# M-LVDS_PHY.net
KiCad netlist of a schematic drawn in Altium Designer
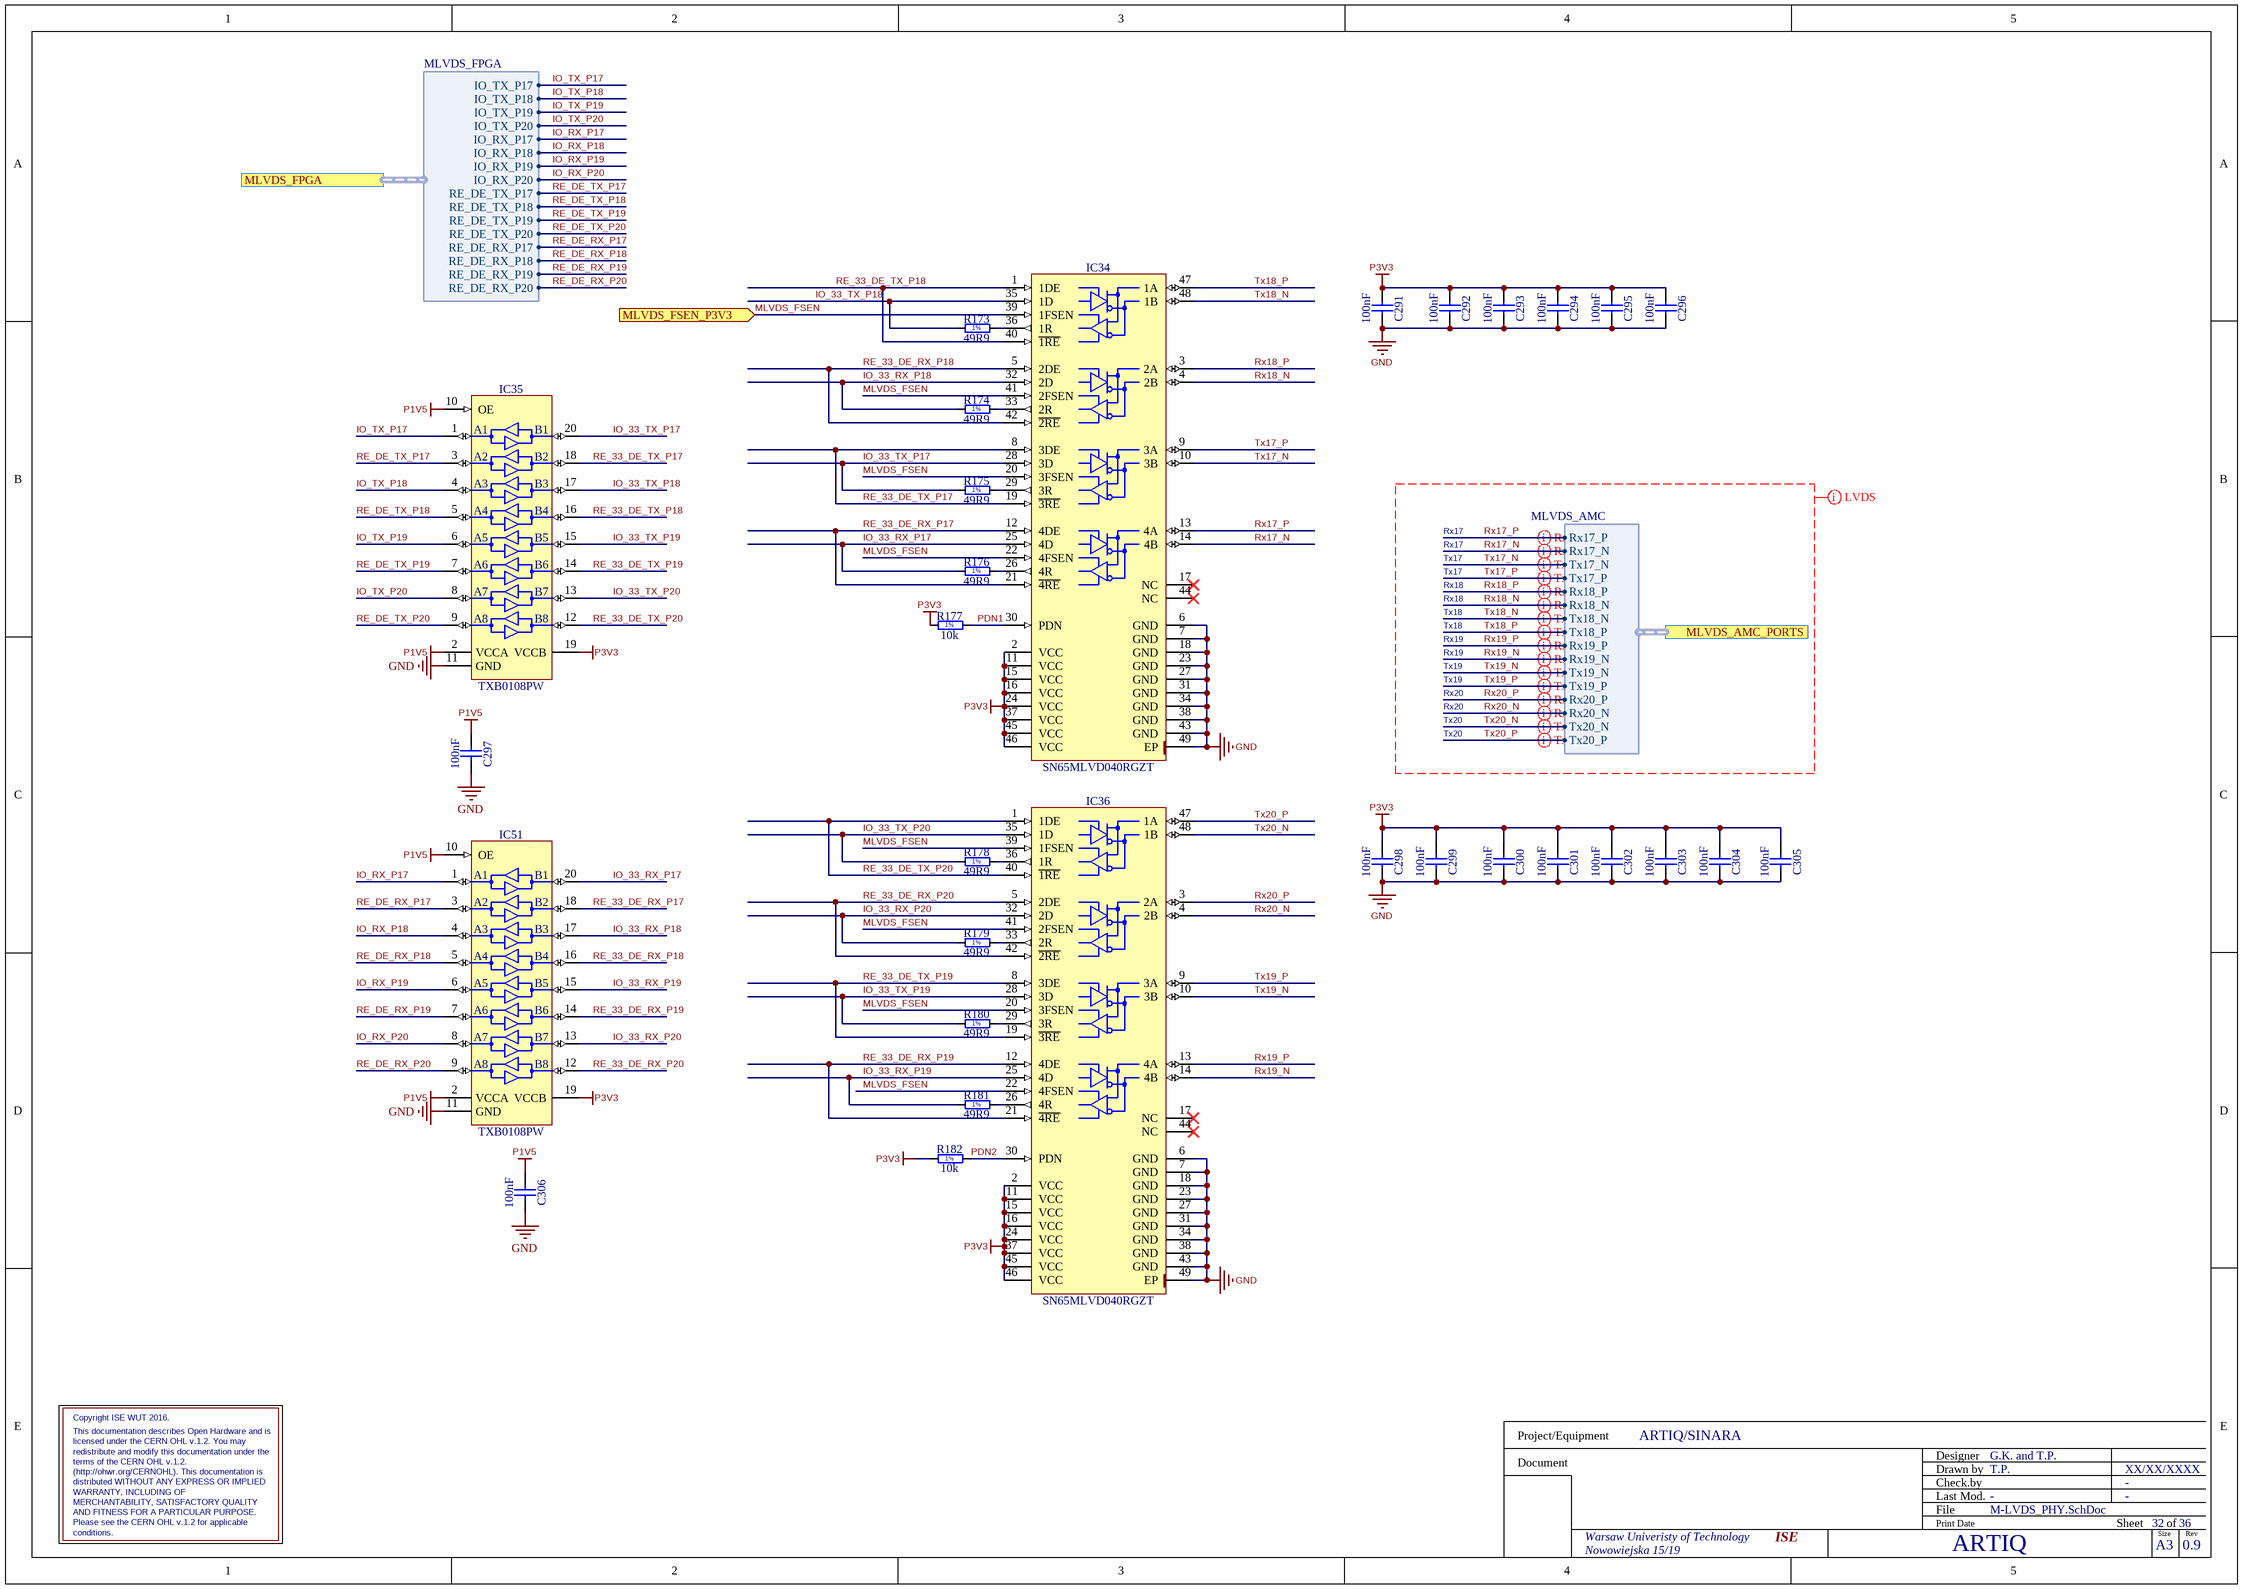
[diagram p0: M-LVDS_PHY.SchDoc]

(export (version "E")
  (design (tool "Eeschema 10.0.6"))
  (components
    (comp (ref "C291")
      (value "100nF")
      (footprint "CAPC0603X33N")
      (description "Non-polarised capacitor")
      (fields
        (field (name "MANUFACTURER PART NUMBER") "CC0201_100NF_6.3V_10%_X5R")
        (field (name "MANUFACTURER") "GENERIC")
        (field (name "AUTHOR") "CERN DEM JLC")
      )
      (libsource (lib "Capacitors") (part "Capacitor - non polarized"))
    )
    (comp (ref "C292")
      (value "100nF")
      (footprint "CAPC0603X33N")
      (description "Non-polarised capacitor")
      (fields
        (field (name "MANUFACTURER PART NUMBER") "CC0201_100NF_6.3V_10%_X5R")
        (field (name "MANUFACTURER") "GENERIC")
        (field (name "AUTHOR") "CERN DEM JLC")
      )
      (libsource (lib "Capacitors") (part "Capacitor - non polarized"))
    )
    (comp (ref "C293")
      (value "100nF")
      (footprint "CAPC0603X33N")
      (description "Non-polarised capacitor")
      (fields
        (field (name "MANUFACTURER PART NUMBER") "CC0201_100NF_6.3V_10%_X5R")
        (field (name "MANUFACTURER") "GENERIC")
        (field (name "AUTHOR") "CERN DEM JLC")
      )
      (libsource (lib "Capacitors") (part "Capacitor - non polarized"))
    )
    (comp (ref "C294")
      (value "100nF")
      (footprint "CAPC0603X33N")
      (description "Non-polarised capacitor")
      (fields
        (field (name "MANUFACTURER PART NUMBER") "CC0201_100NF_6.3V_10%_X5R")
        (field (name "MANUFACTURER") "GENERIC")
        (field (name "AUTHOR") "CERN DEM JLC")
      )
      (libsource (lib "Capacitors") (part "Capacitor - non polarized"))
    )
    (comp (ref "C295")
      (value "100nF")
      (footprint "CAPC0603X33N")
      (description "Non-polarised capacitor")
      (fields
        (field (name "MANUFACTURER PART NUMBER") "CC0201_100NF_6.3V_10%_X5R")
        (field (name "MANUFACTURER") "GENERIC")
        (field (name "AUTHOR") "CERN DEM JLC")
      )
      (libsource (lib "Capacitors") (part "Capacitor - non polarized"))
    )
    (comp (ref "C296")
      (value "100nF")
      (footprint "CAPC0603X33N")
      (description "Non-polarised capacitor")
      (fields
        (field (name "MANUFACTURER PART NUMBER") "CC0201_100NF_6.3V_10%_X5R")
        (field (name "MANUFACTURER") "GENERIC")
        (field (name "AUTHOR") "CERN DEM JLC")
      )
      (libsource (lib "Capacitors") (part "Capacitor - non polarized"))
    )
    (comp (ref "C297")
      (value "100nF")
      (footprint "CAPC0603X33N")
      (description "Non-polarised capacitor")
      (fields
        (field (name "MANUFACTURER PART NUMBER") "CC0201_100NF_6.3V_10%_X5R")
        (field (name "MANUFACTURER") "GENERIC")
        (field (name "AUTHOR") "CERN DEM JLC")
      )
      (libsource (lib "Capacitors") (part "Capacitor - non polarized"))
    )
    (comp (ref "C298")
      (value "100nF")
      (footprint "CAPC0603X33N")
      (description "Non-polarised capacitor")
      (fields
        (field (name "MANUFACTURER PART NUMBER") "CC0201_100NF_6.3V_10%_X5R")
        (field (name "MANUFACTURER") "GENERIC")
        (field (name "AUTHOR") "CERN DEM JLC")
      )
      (libsource (lib "Capacitors") (part "Capacitor - non polarized"))
    )
    (comp (ref "C299")
      (value "100nF")
      (footprint "CAPC0603X33N")
      (description "Non-polarised capacitor")
      (fields
        (field (name "MANUFACTURER PART NUMBER") "CC0201_100NF_6.3V_10%_X5R")
        (field (name "MANUFACTURER") "GENERIC")
        (field (name "AUTHOR") "CERN DEM JLC")
      )
      (libsource (lib "Capacitors") (part "Capacitor - non polarized"))
    )
    (comp (ref "C300")
      (value "100nF")
      (footprint "CAPC0603X33N")
      (description "Non-polarised capacitor")
      (fields
        (field (name "MANUFACTURER PART NUMBER") "CC0201_100NF_6.3V_10%_X5R")
        (field (name "MANUFACTURER") "GENERIC")
        (field (name "AUTHOR") "CERN DEM JLC")
      )
      (libsource (lib "Capacitors") (part "Capacitor - non polarized"))
    )
    (comp (ref "C301")
      (value "100nF")
      (footprint "CAPC0603X33N")
      (description "Non-polarised capacitor")
      (fields
        (field (name "MANUFACTURER PART NUMBER") "CC0201_100NF_6.3V_10%_X5R")
        (field (name "MANUFACTURER") "GENERIC")
        (field (name "AUTHOR") "CERN DEM JLC")
      )
      (libsource (lib "Capacitors") (part "Capacitor - non polarized"))
    )
    (comp (ref "C302")
      (value "100nF")
      (footprint "CAPC0603X33N")
      (description "Non-polarised capacitor")
      (fields
        (field (name "MANUFACTURER PART NUMBER") "CC0201_100NF_6.3V_10%_X5R")
        (field (name "MANUFACTURER") "GENERIC")
        (field (name "AUTHOR") "CERN DEM JLC")
      )
      (libsource (lib "Capacitors") (part "Capacitor - non polarized"))
    )
    (comp (ref "C303")
      (value "100nF")
      (footprint "CAPC0603X33N")
      (description "Non-polarised capacitor")
      (fields
        (field (name "MANUFACTURER PART NUMBER") "CC0201_100NF_6.3V_10%_X5R")
        (field (name "MANUFACTURER") "GENERIC")
        (field (name "AUTHOR") "CERN DEM JLC")
      )
      (libsource (lib "Capacitors") (part "Capacitor - non polarized"))
    )
    (comp (ref "C304")
      (value "100nF")
      (footprint "CAPC0603X33N")
      (description "Non-polarised capacitor")
      (fields
        (field (name "MANUFACTURER PART NUMBER") "CC0201_100NF_6.3V_10%_X5R")
        (field (name "MANUFACTURER") "GENERIC")
        (field (name "AUTHOR") "CERN DEM JLC")
      )
      (libsource (lib "Capacitors") (part "Capacitor - non polarized"))
    )
    (comp (ref "C305")
      (value "100nF")
      (footprint "CAPC0603X33N")
      (description "Non-polarised capacitor")
      (fields
        (field (name "MANUFACTURER PART NUMBER") "CC0201_100NF_6.3V_10%_X5R")
        (field (name "MANUFACTURER") "GENERIC")
        (field (name "AUTHOR") "CERN DEM JLC")
      )
      (libsource (lib "Capacitors") (part "Capacitor - non polarized"))
    )
    (comp (ref "C306")
      (value "100nF")
      (footprint "CAPC0603X33N")
      (description "Non-polarised capacitor")
      (fields
        (field (name "MANUFACTURER PART NUMBER") "CC0201_100NF_6.3V_10%_X5R")
        (field (name "MANUFACTURER") "GENERIC")
        (field (name "AUTHOR") "CERN DEM JLC")
      )
      (libsource (lib "Capacitors") (part "Capacitor - non polarized"))
    )
    (comp (ref "IC34")
      (value "SN65MLVD040RGZT")
      (footprint "QFN50P700X700X100-49N-S420")
      (description "4-Channel Half-Duplex M-LVDS Line Transceiver")
      (fields (field (name "MANUFACTURER") "TEXAS INSTRUMENTS") (field (name "AUTHOR") "CERN DEM JLC"))
      (libsource (lib "ICs And Semiconductors") (part "SN65MLVD040"))
    )
    (comp (ref "IC35")
      (value "TXB0108PW")
      (footprint "SOP65P640X120-20N")
      (fields (field (name "MANUFACTURER") "TEXAS INSTRUMENTS") (field (name "AUTHOR") "CERN DEM MR"))
      (libsource (lib "ICs And Semiconductors") (part "TXB0108PW"))
    )
    (comp (ref "IC36")
      (value "SN65MLVD040RGZT")
      (footprint "QFN50P700X700X100-49N-S420")
      (description "4-Channel Half-Duplex M-LVDS Line Transceiver")
      (fields (field (name "MANUFACTURER") "TEXAS INSTRUMENTS") (field (name "AUTHOR") "CERN DEM JLC"))
      (libsource (lib "ICs And Semiconductors") (part "SN65MLVD040"))
    )
    (comp (ref "IC51")
      (value "TXB0108PW")
      (footprint "SOP65P640X120-20N")
      (fields (field (name "MANUFACTURER") "TEXAS INSTRUMENTS") (field (name "AUTHOR") "CERN DEM MR"))
      (libsource (lib "ICs And Semiconductors") (part "TXB0108PW"))
    )
    (comp (ref "R173")
      (value "49R9")
      (footprint "RESC1005X40N")
      (description "Resistor - 1%")
      (fields
        (field (name "MANUFACTURER PART NUMBER") "R0402_49R9_1%_0.0625W_100PPM")
        (field (name "MANUFACTURER") "GENERIC")
        (field (name "AUTHOR") "CERN DEM JLC")
      )
      (libsource (lib "Resistors") (part "Resistor - 1%"))
    )
    (comp (ref "R174")
      (value "49R9")
      (footprint "RESC1005X40N")
      (description "Resistor - 1%")
      (fields
        (field (name "MANUFACTURER PART NUMBER") "R0402_49R9_1%_0.0625W_100PPM")
        (field (name "MANUFACTURER") "GENERIC")
        (field (name "AUTHOR") "CERN DEM JLC")
      )
      (libsource (lib "Resistors") (part "Resistor - 1%"))
    )
    (comp (ref "R175")
      (value "49R9")
      (footprint "RESC1005X40N")
      (description "Resistor - 1%")
      (fields
        (field (name "MANUFACTURER PART NUMBER") "R0402_49R9_1%_0.0625W_100PPM")
        (field (name "MANUFACTURER") "GENERIC")
        (field (name "AUTHOR") "CERN DEM JLC")
      )
      (libsource (lib "Resistors") (part "Resistor - 1%"))
    )
    (comp (ref "R176")
      (value "49R9")
      (footprint "RESC1005X40N")
      (description "Resistor - 1%")
      (fields
        (field (name "MANUFACTURER PART NUMBER") "R0402_49R9_1%_0.0625W_100PPM")
        (field (name "MANUFACTURER") "GENERIC")
        (field (name "AUTHOR") "CERN DEM JLC")
      )
      (libsource (lib "Resistors") (part "Resistor - 1%"))
    )
    (comp (ref "R177")
      (value "10k")
      (footprint "RESC1005X40N")
      (description "Resistor - 1%")
      (fields
        (field (name "MANUFACTURER PART NUMBER") "R0402_10K_1%_0.0625W_100PPM")
        (field (name "MANUFACTURER") "GENERIC")
        (field (name "AUTHOR") "CERN DEM JLC")
      )
      (libsource (lib "Resistors") (part "Resistor - 1%"))
    )
    (comp (ref "R178")
      (value "49R9")
      (footprint "RESC1005X40N")
      (description "Resistor - 1%")
      (fields
        (field (name "MANUFACTURER PART NUMBER") "R0402_49R9_1%_0.0625W_100PPM")
        (field (name "MANUFACTURER") "GENERIC")
        (field (name "AUTHOR") "CERN DEM JLC")
      )
      (libsource (lib "Resistors") (part "Resistor - 1%"))
    )
    (comp (ref "R179")
      (value "49R9")
      (footprint "RESC1005X40N")
      (description "Resistor - 1%")
      (fields
        (field (name "MANUFACTURER PART NUMBER") "R0402_49R9_1%_0.0625W_100PPM")
        (field (name "MANUFACTURER") "GENERIC")
        (field (name "AUTHOR") "CERN DEM JLC")
      )
      (libsource (lib "Resistors") (part "Resistor - 1%"))
    )
    (comp (ref "R180")
      (value "49R9")
      (footprint "RESC1005X40N")
      (description "Resistor - 1%")
      (fields
        (field (name "MANUFACTURER PART NUMBER") "R0402_49R9_1%_0.0625W_100PPM")
        (field (name "MANUFACTURER") "GENERIC")
        (field (name "AUTHOR") "CERN DEM JLC")
      )
      (libsource (lib "Resistors") (part "Resistor - 1%"))
    )
    (comp (ref "R181")
      (value "49R9")
      (footprint "RESC1005X40N")
      (description "Resistor - 1%")
      (fields
        (field (name "MANUFACTURER PART NUMBER") "R0402_49R9_1%_0.0625W_100PPM")
        (field (name "MANUFACTURER") "GENERIC")
        (field (name "AUTHOR") "CERN DEM JLC")
      )
      (libsource (lib "Resistors") (part "Resistor - 1%"))
    )
    (comp (ref "R182")
      (value "10k")
      (footprint "RESC1005X40N")
      (description "Resistor - 1%")
      (fields
        (field (name "MANUFACTURER PART NUMBER") "R0402_10K_1%_0.0625W_100PPM")
        (field (name "MANUFACTURER") "GENERIC")
        (field (name "AUTHOR") "CERN DEM JLC")
      )
      (libsource (lib "Resistors") (part "Resistor - 1%"))
    )
  )
  (nets
    (net (code "3") (name "/IO_33_RX_P17") (class "Default")
      (node (ref "IC34") (pin "25") (pinfunction "4D_25") (pintype "input"))
      (node (ref "IC51") (pin "20") (pinfunction "B1_20") (pintype "bidirectional"))
      (node (ref "R176") (pin "1") (pinfunction "1_1") (pintype "passive"))
    )
    (net (code "4") (name "/IO_33_RX_P18") (class "Default")
      (node (ref "IC34") (pin "32") (pinfunction "2D_32") (pintype "input"))
      (node (ref "IC51") (pin "17") (pinfunction "B3_17") (pintype "bidirectional"))
      (node (ref "R174") (pin "1") (pinfunction "1_1") (pintype "passive"))
    )
    (net (code "5") (name "/IO_33_RX_P19") (class "Default")
      (node (ref "IC36") (pin "25") (pinfunction "4D_25") (pintype "input"))
      (node (ref "IC51") (pin "15") (pinfunction "B5_15") (pintype "bidirectional"))
      (node (ref "R181") (pin "1") (pinfunction "1_1") (pintype "passive"))
    )
    (net (code "6") (name "/IO_33_RX_P20") (class "Default")
      (node (ref "IC36") (pin "32") (pinfunction "2D_32") (pintype "input"))
      (node (ref "IC51") (pin "13") (pinfunction "B7_13") (pintype "bidirectional"))
      (node (ref "R179") (pin "1") (pinfunction "1_1") (pintype "passive"))
    )
    (net (code "7") (name "/IO_33_TX_P17") (class "Default")
      (node (ref "IC34") (pin "28") (pinfunction "3D_28") (pintype "input"))
      (node (ref "IC35") (pin "20") (pinfunction "B1_20") (pintype "bidirectional"))
      (node (ref "R175") (pin "1") (pinfunction "1_1") (pintype "passive"))
    )
    (net (code "8") (name "/IO_33_TX_P18") (class "Default")
      (node (ref "IC34") (pin "35") (pinfunction "1D_35") (pintype "input"))
      (node (ref "IC35") (pin "17") (pinfunction "B3_17") (pintype "bidirectional"))
      (node (ref "R173") (pin "1") (pinfunction "1_1") (pintype "passive"))
    )
    (net (code "9") (name "/IO_33_TX_P19") (class "Default")
      (node (ref "IC35") (pin "15") (pinfunction "B5_15") (pintype "bidirectional"))
      (node (ref "IC36") (pin "28") (pinfunction "3D_28") (pintype "input"))
      (node (ref "R180") (pin "1") (pinfunction "1_1") (pintype "passive"))
    )
    (net (code "10") (name "/IO_33_TX_P20") (class "Default")
      (node (ref "IC35") (pin "13") (pinfunction "B7_13") (pintype "bidirectional"))
      (node (ref "IC36") (pin "35") (pinfunction "1D_35") (pintype "input"))
      (node (ref "R178") (pin "1") (pinfunction "1_1") (pintype "passive"))
    )
    (net (code "11") (name "/IO_RX_P17") (class "Default")
      (node (ref "IC51") (pin "1") (pinfunction "A1_1") (pintype "bidirectional"))
    )
    (net (code "12") (name "/IO_RX_P18") (class "Default")
      (node (ref "IC51") (pin "4") (pinfunction "A3_4") (pintype "bidirectional"))
    )
    (net (code "13") (name "/IO_RX_P19") (class "Default")
      (node (ref "IC51") (pin "6") (pinfunction "A5_6") (pintype "bidirectional"))
    )
    (net (code "14") (name "/IO_RX_P20") (class "Default")
      (node (ref "IC51") (pin "8") (pinfunction "A7_8") (pintype "bidirectional"))
    )
    (net (code "15") (name "/IO_TX_P17") (class "Default")
      (node (ref "IC35") (pin "1") (pinfunction "A1_1") (pintype "bidirectional"))
    )
    (net (code "16") (name "/IO_TX_P18") (class "Default")
      (node (ref "IC35") (pin "4") (pinfunction "A3_4") (pintype "bidirectional"))
    )
    (net (code "17") (name "/IO_TX_P19") (class "Default")
      (node (ref "IC35") (pin "6") (pinfunction "A5_6") (pintype "bidirectional"))
    )
    (net (code "18") (name "/IO_TX_P20") (class "Default")
      (node (ref "IC35") (pin "8") (pinfunction "A7_8") (pintype "bidirectional"))
    )
    (net (code "19") (name "/MLVDS_FSEN") (class "Default")
      (node (ref "IC34") (pin "20") (pinfunction "3FSEN_20") (pintype "input"))
      (node (ref "IC34") (pin "22") (pinfunction "4FSEN_22") (pintype "input"))
      (node (ref "IC34") (pin "39") (pinfunction "1FSEN_39") (pintype "input"))
      (node (ref "IC34") (pin "41") (pinfunction "2FSEN_41") (pintype "input"))
      (node (ref "IC36") (pin "20") (pinfunction "3FSEN_20") (pintype "input"))
      (node (ref "IC36") (pin "22") (pinfunction "4FSEN_22") (pintype "input"))
      (node (ref "IC36") (pin "39") (pinfunction "1FSEN_39") (pintype "input"))
      (node (ref "IC36") (pin "41") (pinfunction "2FSEN_41") (pintype "input"))
    )
    (net (code "20") (name "/PDN1") (class "Default")
      (node (ref "IC34") (pin "30") (pinfunction "PDN_30") (pintype "input"))
      (node (ref "R177") (pin "2") (pinfunction "2_2") (pintype "passive"))
    )
    (net (code "21") (name "/PDN2") (class "Default")
      (node (ref "IC36") (pin "30") (pinfunction "PDN_30") (pintype "input"))
      (node (ref "R182") (pin "2") (pinfunction "2_2") (pintype "passive"))
    )
    (net (code "22") (name "/RE_33_DE_RX_P17") (class "Default")
      (node (ref "IC34") (pin "12") (pinfunction "4DE_12") (pintype "input"))
      (node (ref "IC34") (pin "21") (pinfunction "~{4RE}_21") (pintype "input"))
      (node (ref "IC51") (pin "18") (pinfunction "B2_18") (pintype "bidirectional"))
    )
    (net (code "23") (name "/RE_33_DE_RX_P18") (class "Default")
      (node (ref "IC34") (pin "42") (pinfunction "~{2RE}_42") (pintype "input"))
      (node (ref "IC34") (pin "5") (pinfunction "2DE_5") (pintype "input"))
      (node (ref "IC51") (pin "16") (pinfunction "B4_16") (pintype "bidirectional"))
    )
    (net (code "24") (name "/RE_33_DE_RX_P19") (class "Default")
      (node (ref "IC36") (pin "12") (pinfunction "4DE_12") (pintype "input"))
      (node (ref "IC36") (pin "21") (pinfunction "~{4RE}_21") (pintype "input"))
      (node (ref "IC51") (pin "14") (pinfunction "B6_14") (pintype "bidirectional"))
    )
    (net (code "25") (name "/RE_33_DE_RX_P20") (class "Default")
      (node (ref "IC36") (pin "42") (pinfunction "~{2RE}_42") (pintype "input"))
      (node (ref "IC36") (pin "5") (pinfunction "2DE_5") (pintype "input"))
      (node (ref "IC51") (pin "12") (pinfunction "B8_12") (pintype "bidirectional"))
    )
    (net (code "26") (name "/RE_33_DE_TX_P17") (class "Default")
      (node (ref "IC34") (pin "19") (pinfunction "~{3RE}_19") (pintype "input"))
      (node (ref "IC34") (pin "8") (pinfunction "3DE_8") (pintype "input"))
      (node (ref "IC35") (pin "18") (pinfunction "B2_18") (pintype "bidirectional"))
    )
    (net (code "27") (name "/RE_33_DE_TX_P18") (class "Default")
      (node (ref "IC34") (pin "1") (pinfunction "1DE_1") (pintype "input"))
      (node (ref "IC34") (pin "40") (pinfunction "~{1RE}_40") (pintype "input"))
      (node (ref "IC35") (pin "16") (pinfunction "B4_16") (pintype "bidirectional"))
    )
    (net (code "28") (name "/RE_33_DE_TX_P19") (class "Default")
      (node (ref "IC35") (pin "14") (pinfunction "B6_14") (pintype "bidirectional"))
      (node (ref "IC36") (pin "19") (pinfunction "~{3RE}_19") (pintype "input"))
      (node (ref "IC36") (pin "8") (pinfunction "3DE_8") (pintype "input"))
    )
    (net (code "29") (name "/RE_33_DE_TX_P20") (class "Default")
      (node (ref "IC35") (pin "12") (pinfunction "B8_12") (pintype "bidirectional"))
      (node (ref "IC36") (pin "1") (pinfunction "1DE_1") (pintype "input"))
      (node (ref "IC36") (pin "40") (pinfunction "~{1RE}_40") (pintype "input"))
    )
    (net (code "30") (name "/RE_DE_RX_P17") (class "Default")
      (node (ref "IC51") (pin "3") (pinfunction "A2_3") (pintype "bidirectional"))
    )
    (net (code "31") (name "/RE_DE_RX_P18") (class "Default")
      (node (ref "IC51") (pin "5") (pinfunction "A4_5") (pintype "bidirectional"))
    )
    (net (code "32") (name "/RE_DE_RX_P19") (class "Default")
      (node (ref "IC51") (pin "7") (pinfunction "A6_7") (pintype "bidirectional"))
    )
    (net (code "33") (name "/RE_DE_RX_P20") (class "Default")
      (node (ref "IC51") (pin "9") (pinfunction "A8_9") (pintype "bidirectional"))
    )
    (net (code "34") (name "/RE_DE_TX_P17") (class "Default")
      (node (ref "IC35") (pin "3") (pinfunction "A2_3") (pintype "bidirectional"))
    )
    (net (code "35") (name "/RE_DE_TX_P18") (class "Default")
      (node (ref "IC35") (pin "5") (pinfunction "A4_5") (pintype "bidirectional"))
    )
    (net (code "36") (name "/RE_DE_TX_P19") (class "Default")
      (node (ref "IC35") (pin "7") (pinfunction "A6_7") (pintype "bidirectional"))
    )
    (net (code "37") (name "/RE_DE_TX_P20") (class "Default")
      (node (ref "IC35") (pin "9") (pinfunction "A8_9") (pintype "bidirectional"))
    )
    (net (code "38") (name "/Rx17_N") (class "Default")
      (node (ref "IC34") (pin "14") (pinfunction "4B_14") (pintype "bidirectional"))
    )
    (net (code "39") (name "/Rx17_P") (class "Default")
      (node (ref "IC34") (pin "13") (pinfunction "4A_13") (pintype "bidirectional"))
    )
    (net (code "40") (name "/Rx18_N") (class "Default")
      (node (ref "IC34") (pin "4") (pinfunction "2B_4") (pintype "bidirectional"))
    )
    (net (code "41") (name "/Rx18_P") (class "Default")
      (node (ref "IC34") (pin "3") (pinfunction "2A_3") (pintype "bidirectional"))
    )
    (net (code "42") (name "/Rx19_N") (class "Default")
      (node (ref "IC36") (pin "14") (pinfunction "4B_14") (pintype "bidirectional"))
    )
    (net (code "43") (name "/Rx19_P") (class "Default")
      (node (ref "IC36") (pin "13") (pinfunction "4A_13") (pintype "bidirectional"))
    )
    (net (code "44") (name "/Rx20_N") (class "Default")
      (node (ref "IC36") (pin "4") (pinfunction "2B_4") (pintype "bidirectional"))
    )
    (net (code "45") (name "/Rx20_P") (class "Default")
      (node (ref "IC36") (pin "3") (pinfunction "2A_3") (pintype "bidirectional"))
    )
    (net (code "46") (name "/Tx17_N") (class "Default")
      (node (ref "IC34") (pin "10") (pinfunction "3B_10") (pintype "bidirectional"))
    )
    (net (code "47") (name "/Tx17_P") (class "Default")
      (node (ref "IC34") (pin "9") (pinfunction "3A_9") (pintype "bidirectional"))
    )
    (net (code "48") (name "/Tx18_N") (class "Default")
      (node (ref "IC34") (pin "48") (pinfunction "1B_48") (pintype "bidirectional"))
    )
    (net (code "49") (name "/Tx18_P") (class "Default")
      (node (ref "IC34") (pin "47") (pinfunction "1A_47") (pintype "bidirectional"))
    )
    (net (code "50") (name "/Tx19_N") (class "Default")
      (node (ref "IC36") (pin "10") (pinfunction "3B_10") (pintype "bidirectional"))
    )
    (net (code "51") (name "/Tx19_P") (class "Default")
      (node (ref "IC36") (pin "9") (pinfunction "3A_9") (pintype "bidirectional"))
    )
    (net (code "52") (name "/Tx20_N") (class "Default")
      (node (ref "IC36") (pin "48") (pinfunction "1B_48") (pintype "bidirectional"))
    )
    (net (code "53") (name "/Tx20_P") (class "Default")
      (node (ref "IC36") (pin "47") (pinfunction "1A_47") (pintype "bidirectional"))
    )
    (net (code "56") (name "GND") (class "Default")
      (node (ref "C291") (pin "2") (pinfunction "2_2") (pintype "passive"))
      (node (ref "C292") (pin "2") (pinfunction "2_2") (pintype "passive"))
      (node (ref "C293") (pin "2") (pinfunction "2_2") (pintype "passive"))
      (node (ref "C294") (pin "2") (pinfunction "2_2") (pintype "passive"))
      (node (ref "C295") (pin "2") (pinfunction "2_2") (pintype "passive"))
      (node (ref "C296") (pin "2") (pinfunction "2_2") (pintype "passive"))
      (node (ref "C297") (pin "2") (pinfunction "2_2") (pintype "passive"))
      (node (ref "C298") (pin "2") (pinfunction "2_2") (pintype "passive"))
      (node (ref "C299") (pin "2") (pinfunction "2_2") (pintype "passive"))
      (node (ref "C300") (pin "2") (pinfunction "2_2") (pintype "passive"))
      (node (ref "C301") (pin "2") (pinfunction "2_2") (pintype "passive"))
      (node (ref "C302") (pin "2") (pinfunction "2_2") (pintype "passive"))
      (node (ref "C303") (pin "2") (pinfunction "2_2") (pintype "passive"))
      (node (ref "C304") (pin "2") (pinfunction "2_2") (pintype "passive"))
      (node (ref "C305") (pin "2") (pinfunction "2_2") (pintype "passive"))
      (node (ref "C306") (pin "2") (pinfunction "2_2") (pintype "passive"))
      (node (ref "IC34") (pin "18") (pinfunction "GND_18") (pintype "power_in"))
      (node (ref "IC34") (pin "23") (pinfunction "GND_23") (pintype "power_in"))
      (node (ref "IC34") (pin "27") (pinfunction "GND_27") (pintype "power_in"))
      (node (ref "IC34") (pin "31") (pinfunction "GND_31") (pintype "power_in"))
      (node (ref "IC34") (pin "34") (pinfunction "GND_34") (pintype "power_in"))
      (node (ref "IC34") (pin "38") (pinfunction "GND_38") (pintype "power_in"))
      (node (ref "IC34") (pin "43") (pinfunction "GND_43") (pintype "power_in"))
      (node (ref "IC34") (pin "49") (pinfunction "EP_49") (pintype "power_in"))
      (node (ref "IC34") (pin "6") (pinfunction "GND_6") (pintype "power_in"))
      (node (ref "IC34") (pin "7") (pinfunction "GND_7") (pintype "power_in"))
      (node (ref "IC35") (pin "11") (pinfunction "GND_11") (pintype "power_in"))
      (node (ref "IC36") (pin "18") (pinfunction "GND_18") (pintype "power_in"))
      (node (ref "IC36") (pin "23") (pinfunction "GND_23") (pintype "power_in"))
      (node (ref "IC36") (pin "27") (pinfunction "GND_27") (pintype "power_in"))
      (node (ref "IC36") (pin "31") (pinfunction "GND_31") (pintype "power_in"))
      (node (ref "IC36") (pin "34") (pinfunction "GND_34") (pintype "power_in"))
      (node (ref "IC36") (pin "38") (pinfunction "GND_38") (pintype "power_in"))
      (node (ref "IC36") (pin "43") (pinfunction "GND_43") (pintype "power_in"))
      (node (ref "IC36") (pin "49") (pinfunction "EP_49") (pintype "power_in"))
      (node (ref "IC36") (pin "6") (pinfunction "GND_6") (pintype "power_in"))
      (node (ref "IC36") (pin "7") (pinfunction "GND_7") (pintype "power_in"))
      (node (ref "IC51") (pin "11") (pinfunction "GND_11") (pintype "power_in"))
    )
    (net (code "57") (name "Net-(IC34-1R)") (class "Default")
      (node (ref "IC34") (pin "36") (pinfunction "1R_36") (pintype "output"))
      (node (ref "R173") (pin "2") (pinfunction "2_2") (pintype "passive"))
    )
    (net (code "58") (name "Net-(IC34-2R)") (class "Default")
      (node (ref "IC34") (pin "33") (pinfunction "2R_33") (pintype "output"))
      (node (ref "R174") (pin "2") (pinfunction "2_2") (pintype "passive"))
    )
    (net (code "59") (name "Net-(IC34-3R)") (class "Default")
      (node (ref "IC34") (pin "29") (pinfunction "3R_29") (pintype "output"))
      (node (ref "R175") (pin "2") (pinfunction "2_2") (pintype "passive"))
    )
    (net (code "60") (name "Net-(IC34-4R)") (class "Default")
      (node (ref "IC34") (pin "26") (pinfunction "4R_26") (pintype "output"))
      (node (ref "R176") (pin "2") (pinfunction "2_2") (pintype "passive"))
    )
    (net (code "61") (name "Net-(IC36-1R)") (class "Default")
      (node (ref "IC36") (pin "36") (pinfunction "1R_36") (pintype "output"))
      (node (ref "R178") (pin "2") (pinfunction "2_2") (pintype "passive"))
    )
    (net (code "62") (name "Net-(IC36-2R)") (class "Default")
      (node (ref "IC36") (pin "33") (pinfunction "2R_33") (pintype "output"))
      (node (ref "R179") (pin "2") (pinfunction "2_2") (pintype "passive"))
    )
    (net (code "63") (name "Net-(IC36-3R)") (class "Default")
      (node (ref "IC36") (pin "29") (pinfunction "3R_29") (pintype "output"))
      (node (ref "R180") (pin "2") (pinfunction "2_2") (pintype "passive"))
    )
    (net (code "64") (name "Net-(IC36-4R)") (class "Default")
      (node (ref "IC36") (pin "26") (pinfunction "4R_26") (pintype "output"))
      (node (ref "R181") (pin "2") (pinfunction "2_2") (pintype "passive"))
    )
    (net (code "65") (name "P1V5") (class "Default")
      (node (ref "C297") (pin "1") (pinfunction "1_1") (pintype "passive"))
      (node (ref "C306") (pin "1") (pinfunction "1_1") (pintype "passive"))
      (node (ref "IC35") (pin "10") (pinfunction "OE_10") (pintype "input"))
      (node (ref "IC35") (pin "2") (pinfunction "Vcca_2") (pintype "power_in"))
      (node (ref "IC51") (pin "10") (pinfunction "OE_10") (pintype "input"))
      (node (ref "IC51") (pin "2") (pinfunction "Vcca_2") (pintype "power_in"))
    )
    (net (code "66") (name "P3V3") (class "Default")
      (node (ref "C291") (pin "1") (pinfunction "1_1") (pintype "passive"))
      (node (ref "C292") (pin "1") (pinfunction "1_1") (pintype "passive"))
      (node (ref "C293") (pin "1") (pinfunction "1_1") (pintype "passive"))
      (node (ref "C294") (pin "1") (pinfunction "1_1") (pintype "passive"))
      (node (ref "C295") (pin "1") (pinfunction "1_1") (pintype "passive"))
      (node (ref "C296") (pin "1") (pinfunction "1_1") (pintype "passive"))
      (node (ref "C298") (pin "1") (pinfunction "1_1") (pintype "passive"))
      (node (ref "C299") (pin "1") (pinfunction "1_1") (pintype "passive"))
      (node (ref "C300") (pin "1") (pinfunction "1_1") (pintype "passive"))
      (node (ref "C301") (pin "1") (pinfunction "1_1") (pintype "passive"))
      (node (ref "C302") (pin "1") (pinfunction "1_1") (pintype "passive"))
      (node (ref "C303") (pin "1") (pinfunction "1_1") (pintype "passive"))
      (node (ref "C304") (pin "1") (pinfunction "1_1") (pintype "passive"))
      (node (ref "C305") (pin "1") (pinfunction "1_1") (pintype "passive"))
      (node (ref "IC34") (pin "11") (pinfunction "VCC_11") (pintype "power_in"))
      (node (ref "IC34") (pin "15") (pinfunction "VCC_15") (pintype "power_in"))
      (node (ref "IC34") (pin "16") (pinfunction "VCC_16") (pintype "power_in"))
      (node (ref "IC34") (pin "2") (pinfunction "VCC_2") (pintype "power_in"))
      (node (ref "IC34") (pin "24") (pinfunction "VCC_24") (pintype "power_in"))
      (node (ref "IC34") (pin "37") (pinfunction "VCC_37") (pintype "power_in"))
      (node (ref "IC34") (pin "45") (pinfunction "VCC_45") (pintype "power_in"))
      (node (ref "IC34") (pin "46") (pinfunction "VCC_46") (pintype "power_in"))
      (node (ref "IC35") (pin "19") (pinfunction "Vccb_19") (pintype "power_in"))
      (node (ref "IC36") (pin "11") (pinfunction "VCC_11") (pintype "power_in"))
      (node (ref "IC36") (pin "15") (pinfunction "VCC_15") (pintype "power_in"))
      (node (ref "IC36") (pin "16") (pinfunction "VCC_16") (pintype "power_in"))
      (node (ref "IC36") (pin "2") (pinfunction "VCC_2") (pintype "power_in"))
      (node (ref "IC36") (pin "24") (pinfunction "VCC_24") (pintype "power_in"))
      (node (ref "IC36") (pin "37") (pinfunction "VCC_37") (pintype "power_in"))
      (node (ref "IC36") (pin "45") (pinfunction "VCC_45") (pintype "power_in"))
      (node (ref "IC36") (pin "46") (pinfunction "VCC_46") (pintype "power_in"))
      (node (ref "IC51") (pin "19") (pinfunction "Vccb_19") (pintype "power_in"))
      (node (ref "R177") (pin "1") (pinfunction "1_1") (pintype "passive"))
      (node (ref "R182") (pin "1") (pinfunction "1_1") (pintype "passive"))
    )
    (net (code "67") (name "unconnected-(IC34-NC-Pad17)") (class "Default")
      (node (ref "IC34") (pin "17") (pinfunction "NC_17") (pintype "passive+no_connect"))
    )
    (net (code "68") (name "unconnected-(IC34-NC-Pad44)") (class "Default")
      (node (ref "IC34") (pin "44") (pinfunction "NC_44") (pintype "passive+no_connect"))
    )
    (net (code "69") (name "unconnected-(IC36-NC-Pad17)") (class "Default")
      (node (ref "IC36") (pin "17") (pinfunction "NC_17") (pintype "passive+no_connect"))
    )
    (net (code "70") (name "unconnected-(IC36-NC-Pad44)") (class "Default")
      (node (ref "IC36") (pin "44") (pinfunction "NC_44") (pintype "passive+no_connect"))
    )
  )
)
